# dcdc_0421.net
KiCad netlist of a schematic drawn in EAGLE
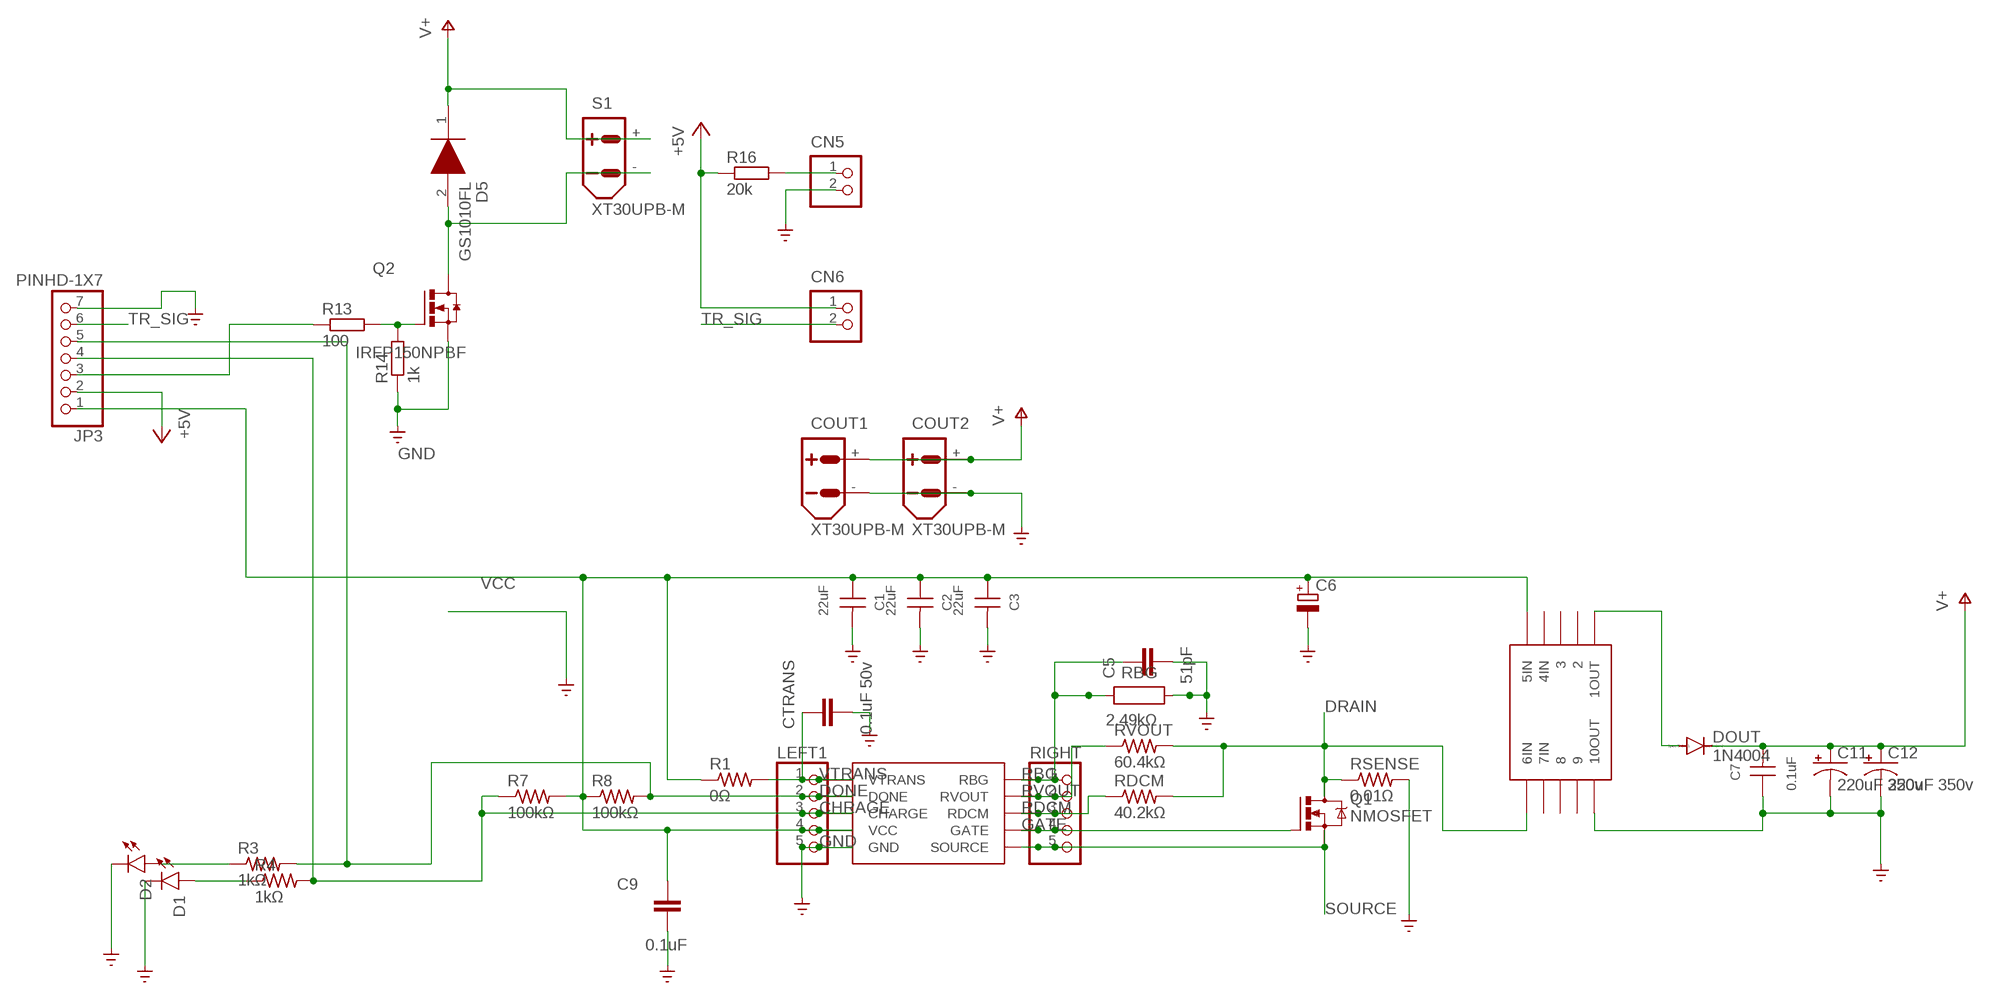
[diagram p0: schematic, sheet 1]

(export (version "E")
  (design (tool "Eeschema 10.0.6"))
  (components
    (comp (ref "C1")
      (value "22uF")
      (footprint "eagle-import:WCAP-CSGP_1210_H0.95")
      (libsource (lib "eagle-import") (part "WCAP-CSGP_1210_H0.95_25V(DC)_885012009002"))
    )
    (comp (ref "C2")
      (value "22uF")
      (footprint "eagle-import:WCAP-CSGP_1210_H0.95")
      (libsource (lib "eagle-import") (part "WCAP-CSGP_1210_H0.95_25V(DC)_885012009002"))
    )
    (comp (ref "C3")
      (value "22uF")
      (footprint "eagle-import:WCAP-CSGP_1210_H0.95")
      (libsource (lib "eagle-import") (part "WCAP-CSGP_1210_H0.95_25V(DC)_885012009002"))
    )
    (comp (ref "C5")
      (value "51pF")
      (footprint "eagle-import:CAP_0603")
      (fields
        (field (name "DIGIKEY_PART_NUMBER") "399-7814-2-ND")
        (field (name "MANUFACTURER") "KEMET")
        (field (name "MPN") "C0603C100C5GACTU")
        (field (name "CREATED_BY") "PCBLayout.com")
      )
      (libsource (lib "eagle-import") (part "C0603C100C5GACTU"))
    )
    (comp (ref "C6")
      (value "CPOL-EUTT2D6")
      (footprint "eagle-import:TT2D6")
      (libsource (lib "eagle-import") (part "CPOL-EUTT2D6"))
    )
    (comp (ref "C7")
      (value "0.1uF")
      (footprint "eagle-import:WCAP-CSGP_1812_H1.25")
      (libsource (lib "eagle-import") (part "WCAP-CSGP_1812_H1.25_16V(DC)_885012010001"))
    )
    (comp (ref "C9")
      (value "0.1uF")
      (footprint "eagle-import:CAP_0603")
      (fields
        (field (name "DIGIKEY_PART_NUMBER") "399-7814-2-ND")
        (field (name "MANUFACTURER") "KEMET")
        (field (name "MPN") "C0603C100C5GACTU")
        (field (name "CREATED_BY") "PCBLayout.com")
      )
      (libsource (lib "eagle-import") (part "C0603C100C5GACTU"))
    )
    (comp (ref "C11")
      (value "220uF 350v")
      (footprint "eagle-import:E7,5-18")
      (libsource (lib "eagle-import") (part "CAPACITOR-PE7.5-18"))
    )
    (comp (ref "C12")
      (value "220uF 350v")
      (footprint "eagle-import:E7,5-18")
      (libsource (lib "eagle-import") (part "CAPACITOR-PE7.5-18"))
    )
    (comp (ref "CN5")
      (value "S2B-XH-A")
      (footprint "eagle-import:S2B-XH-A")
      (libsource (lib "eagle-import") (part "S2B-XH-A"))
    )
    (comp (ref "CN6")
      (value "S2B-XH-A")
      (footprint "eagle-import:S2B-XH-A")
      (libsource (lib "eagle-import") (part "S2B-XH-A"))
    )
    (comp (ref "COUT1")
      (value "XT30UPB-M")
      (footprint "eagle-import:XT30UPB-M")
      (libsource (lib "eagle-import") (part "XT30UPB-M"))
    )
    (comp (ref "COUT2")
      (value "XT30UPB-M")
      (footprint "eagle-import:XT30UPB-M")
      (libsource (lib "eagle-import") (part "XT30UPB-M"))
    )
    (comp (ref "CTRANS")
      (value "0.1uF 50v")
      (footprint "eagle-import:CAP_1206")
      (fields
        (field (name "DIGIKEY_PART_NUMBER") "GRM31CR60J107ME39L")
        (field (name "MANUFACTURER") "Murata Electronics North America")
        (field (name "CREATED_BY") "PCBLayout.com")
      )
      (libsource (lib "eagle-import") (part "GRM31CR60J107ME39L"))
    )
    (comp (ref "D1")
      (value "LED_RADIALWHITE")
      (footprint "eagle-import:LEDRD254W60D565H860B_W")
      (libsource (lib "eagle-import") (part "LED_RADIALWHITE"))
    )
    (comp (ref "D2")
      (value "LED_RADIALWHITE")
      (footprint "eagle-import:LEDRD254W60D565H860B_W")
      (libsource (lib "eagle-import") (part "LED_RADIALWHITE"))
    )
    (comp (ref "D5")
      (value "GS1010FL")
      (footprint "eagle-import:SODFL3618X110N")
      (libsource (lib "eagle-import") (part "GS1010FL"))
    )
    (comp (ref "DOUT")
      (value "1N4004")
      (footprint "eagle-import:DO41-10")
      (libsource (lib "eagle-import") (part "1N4004"))
    )
    (comp (ref "JP3")
      (value "PINHD-1X7")
      (footprint "eagle-import:1X07")
      (libsource (lib "eagle-import") (part "PINHD-1X7"))
    )
    (comp (ref "LEFT1")
      (value "PINHD-1X5")
      (footprint "eagle-import:1X05")
      (libsource (lib "eagle-import") (part "PINHD-1X5"))
    )
    (comp (ref "Q1")
      (value "NMOSFET")
      (footprint "eagle-import:TO220BV")
      (libsource (lib "eagle-import") (part "NMOSFET_TO220_"))
    )
    (comp (ref "Q2")
      (value "IRFP150NPBF")
      (footprint "eagle-import:TO-247AC")
      (fields
        (field (name "DIGIKEY_PART_NUMBER") "IRFP150NPBF-ND")
        (field (name "CREATED_BY") "PCBLayout.com")
      )
      (libsource (lib "eagle-import") (part "IRFP150NPBF"))
    )
    (comp (ref "R1")
      (value "0Ω")
      (footprint "eagle-import:M2012")
      (libsource (lib "eagle-import") (part "R-US_M2012"))
    )
    (comp (ref "R3")
      (value "1kΩ")
      (footprint "eagle-import:RES_0402")
      (fields
        (field (name "DIGIKEY_PART_NUMBER") "311-0.0JRTR-ND")
        (field (name "MANUFACTURER") "Yageo")
        (field (name "MPN") "RC0402JR-070RL")
        (field (name "CREATED_BY") "PCBLayout.com")
      )
      (libsource (lib "eagle-import") (part "RC0402JR-070RL"))
    )
    (comp (ref "R4")
      (value "1kΩ")
      (footprint "eagle-import:RES_0402")
      (fields
        (field (name "DIGIKEY_PART_NUMBER") "311-0.0JRTR-ND")
        (field (name "MANUFACTURER") "Yageo")
        (field (name "MPN") "RC0402JR-070RL")
        (field (name "CREATED_BY") "PCBLayout.com")
      )
      (libsource (lib "eagle-import") (part "RC0402JR-070RL"))
    )
    (comp (ref "R7")
      (value "100kΩ")
      (footprint "eagle-import:R1210")
      (libsource (lib "eagle-import") (part "R-US_R1210"))
    )
    (comp (ref "R8")
      (value "100kΩ")
      (footprint "eagle-import:R1210")
      (libsource (lib "eagle-import") (part "R-US_R1210"))
    )
    (comp (ref "R13")
      (value "100")
      (footprint "eagle-import:R0603")
      (libsource (lib "eagle-import") (part "R-EU_R0603"))
    )
    (comp (ref "R14")
      (value "1k")
      (footprint "eagle-import:R0603")
      (libsource (lib "eagle-import") (part "R-EU_R0603"))
    )
    (comp (ref "R16")
      (value "20k")
      (footprint "eagle-import:R0603")
      (libsource (lib "eagle-import") (part "R-EU_R0603"))
    )
    (comp (ref "RBG")
      (value "2.49kΩ")
      (footprint "eagle-import:WRIS_PSMC_2512_6.3X3.1X0.51X1.1(LXWXHXPW)")
      (libsource (lib "eagle-import") (part "WRIS-PSMC_2512_6.3X3.1X0.51X1.1_580070763005"))
    )
    (comp (ref "RDCM")
      (value "40.2kΩ")
      (footprint "eagle-import:RES_0805")
      (fields
        (field (name "DIGIKEY_PART_NUMBER") "541-0.0ATR-ND")
        (field (name "MANUFACTURER") "Vishay Dale")
        (field (name "MPN") "CRCW08050000Z0EA")
        (field (name "CREATED_BY") "PCBLayout.com")
      )
      (libsource (lib "eagle-import") (part "CRCW08050000Z0EA"))
    )
    (comp (ref "RIGHT")
      (value "PINHD-1X5")
      (footprint "eagle-import:1X05")
      (libsource (lib "eagle-import") (part "PINHD-1X5"))
    )
    (comp (ref "RSENSE")
      (value "0.01Ω")
      (footprint "eagle-import:RES_1206")
      (fields
        (field (name "DIGIKEY_PART_NUMBER") "WSLP-.05TR-ND")
        (field (name "MANUFACTURER") "Vishay Dale")
        (field (name "MPN") "WSLP1206R0500FEA")
        (field (name "CREATED_BY") "PCBLayout.com")
      )
      (libsource (lib "eagle-import") (part "WSLP1206R0500FEA"))
    )
    (comp (ref "RVOUT")
      (value "60.4kΩ")
      (footprint "eagle-import:RES_0805")
      (fields
        (field (name "DIGIKEY_PART_NUMBER") "541-0.0ATR-ND")
        (field (name "MANUFACTURER") "Vishay Dale")
        (field (name "MPN") "CRCW08050000Z0EA")
        (field (name "CREATED_BY") "PCBLayout.com")
      )
      (libsource (lib "eagle-import") (part "CRCW08050000Z0EA"))
    )
    (comp (ref "S1")
      (value "XT30UPB-M")
      (footprint "eagle-import:XT30UPB-M")
      (libsource (lib "eagle-import") (part "XT30UPB-M"))
    )
    (comp (ref "U$1")
      (value "LT3750_2")
      (footprint "eagle-import:LT3750_2")
      (libsource (lib "eagle-import") (part "LT3750_2"))
    )
    (comp (ref "U$2")
      (value "32052")
      (footprint "eagle-import:32052")
      (libsource (lib "eagle-import") (part "32052"))
    )
  )
  (nets
    (net (code "1") (name "+5V") (class "Default")
      (node (ref "CN6") (pin "1") (pinfunction "1_1") (pintype "passive"))
      (node (ref "JP3") (pin "2") (pinfunction "2_2") (pintype "passive"))
      (node (ref "R16") (pin "1") (pinfunction "1_1") (pintype "passive"))
    )
    (net (code "2") (name "/CHRAGE") (class "Default")
      (node (ref "JP3") (pin "4") (pinfunction "4_4") (pintype "passive"))
      (node (ref "LEFT1") (pin "3") (pinfunction "3_3") (pintype "passive"))
      (node (ref "R4") (pin "2") (pinfunction "2_2") (pintype "passive"))
      (node (ref "R7") (pin "1") (pinfunction "1_1") (pintype "passive"))
      (node (ref "U$1") (pin "CHARGE") (pinfunction "CHARGE_CHARGE") (pintype "bidirectional"))
    )
    (net (code "3") (name "/DONE") (class "Default")
      (node (ref "JP3") (pin "5") (pinfunction "5_5") (pintype "passive"))
      (node (ref "LEFT1") (pin "2") (pinfunction "2_2") (pintype "passive"))
      (node (ref "R3") (pin "2") (pinfunction "2_2") (pintype "passive"))
      (node (ref "R8") (pin "2") (pinfunction "2_2") (pintype "passive"))
      (node (ref "U$1") (pin "DONE") (pinfunction "DONE_DONE") (pintype "bidirectional"))
    )
    (net (code "4") (name "/DRAIN") (class "Default")
      (node (ref "Q1") (pin "D") (pinfunction "D_D") (pintype "passive"))
      (node (ref "RDCM") (pin "2") (pinfunction "2_2") (pintype "passive"))
      (node (ref "RSENSE") (pin "1") (pinfunction "1_1") (pintype "passive"))
      (node (ref "RVOUT") (pin "2") (pinfunction "2_2") (pintype "passive"))
      (node (ref "U$2") (pin "6IN") (pinfunction "6IN_6IN") (pintype "bidirectional"))
    )
    (net (code "5") (name "/GATE") (class "Default")
      (node (ref "Q1") (pin "G") (pinfunction "G_G") (pintype "passive"))
      (node (ref "RIGHT") (pin "4") (pinfunction "4_4") (pintype "passive"))
      (node (ref "U$1") (pin "GATE") (pinfunction "GATE_GATE") (pintype "bidirectional"))
    )
    (net (code "6") (name "/RBG") (class "Default")
      (node (ref "C5") (pin "1") (pinfunction "1_1") (pintype "passive"))
      (node (ref "RBG") (pin "1") (pinfunction "1_1") (pintype "passive"))
      (node (ref "RIGHT") (pin "1") (pinfunction "1_1") (pintype "passive"))
      (node (ref "U$1") (pin "RBG") (pinfunction "RBG_RBG") (pintype "bidirectional"))
    )
    (net (code "7") (name "/RDCM") (class "Default")
      (node (ref "RDCM") (pin "1") (pinfunction "1_1") (pintype "passive"))
      (node (ref "RIGHT") (pin "3") (pinfunction "3_3") (pintype "passive"))
      (node (ref "U$1") (pin "RDCM") (pinfunction "RDCM_RDCM") (pintype "bidirectional"))
    )
    (net (code "8") (name "/RVOUT") (class "Default")
      (node (ref "RIGHT") (pin "2") (pinfunction "2_2") (pintype "passive"))
      (node (ref "RVOUT") (pin "1") (pinfunction "1_1") (pintype "passive"))
      (node (ref "U$1") (pin "RVOUT") (pinfunction "RVOUT_RVOUT") (pintype "bidirectional"))
    )
    (net (code "9") (name "/SOURCE") (class "Default")
      (node (ref "Q1") (pin "S") (pinfunction "S_S") (pintype "passive"))
      (node (ref "RIGHT") (pin "5") (pinfunction "5_5") (pintype "passive"))
      (node (ref "U$1") (pin "SOURCE") (pinfunction "SOURCE_SOURCE") (pintype "bidirectional"))
    )
    (net (code "10") (name "/TR_SIG") (class "Default")
      (node (ref "CN6") (pin "2") (pinfunction "2_2") (pintype "passive"))
      (node (ref "JP3") (pin "6") (pinfunction "6_6") (pintype "passive"))
    )
    (net (code "11") (name "/VCC") (class "Default")
      (node (ref "C1") (pin "1") (pinfunction "1_1") (pintype "passive"))
      (node (ref "C2") (pin "1") (pinfunction "1_1") (pintype "passive"))
      (node (ref "C3") (pin "1") (pinfunction "1_1") (pintype "passive"))
      (node (ref "C6") (pin "+") (pinfunction "+_+") (pintype "passive"))
      (node (ref "C9") (pin "1") (pinfunction "1_1") (pintype "passive"))
      (node (ref "JP3") (pin "1") (pinfunction "1_1") (pintype "passive"))
      (node (ref "LEFT1") (pin "4") (pinfunction "4_4") (pintype "passive"))
      (node (ref "R1") (pin "1") (pinfunction "1_1") (pintype "passive"))
      (node (ref "R7") (pin "2") (pinfunction "2_2") (pintype "passive"))
      (node (ref "R8") (pin "1") (pinfunction "1_1") (pintype "passive"))
      (node (ref "U$1") (pin "VCC") (pinfunction "VCC_VCC") (pintype "bidirectional"))
      (node (ref "U$2") (pin "5IN") (pinfunction "5IN_5IN") (pintype "bidirectional"))
    )
    (net (code "12") (name "/VTRANS") (class "Default")
      (node (ref "CTRANS") (pin "1") (pinfunction "1_1") (pintype "passive"))
      (node (ref "LEFT1") (pin "1") (pinfunction "1_1") (pintype "passive"))
      (node (ref "R1") (pin "2") (pinfunction "2_2") (pintype "passive"))
      (node (ref "U$1") (pin "VTRANS") (pinfunction "VTRANS_VTRANS") (pintype "bidirectional"))
    )
    (net (code "13") (name "Net-(CN5-Pad1)") (class "Default")
      (node (ref "CN5") (pin "1") (pinfunction "1_1") (pintype "passive"))
      (node (ref "R16") (pin "2") (pinfunction "2_2") (pintype "passive"))
    )
    (net (code "14") (name "Net-(D1-PadA)") (class "Default")
      (node (ref "D1") (pin "A") (pinfunction "A_A") (pintype "passive"))
      (node (ref "R4") (pin "1") (pinfunction "1_1") (pintype "passive"))
    )
    (net (code "15") (name "Net-(D2-PadA)") (class "Default")
      (node (ref "D2") (pin "A") (pinfunction "A_A") (pintype "passive"))
      (node (ref "R3") (pin "1") (pinfunction "1_1") (pintype "passive"))
    )
    (net (code "16") (name "Net-(D5-A)") (class "Default")
      (node (ref "D5") (pin "2") (pinfunction "A_2") (pintype "bidirectional"))
      (node (ref "Q2") (pin "D") (pinfunction "D_D") (pintype "passive"))
      (node (ref "S1") (pin "-") (pinfunction "-_-") (pintype "power_in"))
    )
    (net (code "17") (name "Net-(DOUT-PadA)") (class "Default")
      (node (ref "DOUT") (pin "A") (pinfunction "A_A") (pintype "passive"))
      (node (ref "U$2") (pin "1OUT") (pinfunction "1OUT_1OUT") (pintype "bidirectional"))
    )
    (net (code "18") (name "Net-(JP3-Pad3)") (class "Default")
      (node (ref "JP3") (pin "3") (pinfunction "3_3") (pintype "passive"))
      (node (ref "R13") (pin "1") (pinfunction "1_1") (pintype "passive"))
    )
    (net (code "19") (name "Net-(Q2-PadG)") (class "Default")
      (node (ref "Q2") (pin "G") (pinfunction "G_G") (pintype "passive"))
      (node (ref "R13") (pin "2") (pinfunction "2_2") (pintype "passive"))
      (node (ref "R14") (pin "2") (pinfunction "2_2") (pintype "passive"))
    )
    (net (code "20") (name "SUPPLY0_GND_") (class "Default")
      (node (ref "C1") (pin "2") (pinfunction "2_2") (pintype "passive"))
      (node (ref "C11") (pin "-") (pinfunction "-_-") (pintype "passive"))
      (node (ref "C12") (pin "-") (pinfunction "-_-") (pintype "passive"))
      (node (ref "C2") (pin "2") (pinfunction "2_2") (pintype "passive"))
      (node (ref "C3") (pin "2") (pinfunction "2_2") (pintype "passive"))
      (node (ref "C5") (pin "2") (pinfunction "2_2") (pintype "passive"))
      (node (ref "C6") (pin "-") (pinfunction "-_-") (pintype "passive"))
      (node (ref "C7") (pin "1") (pinfunction "1_1") (pintype "passive"))
      (node (ref "C9") (pin "2") (pinfunction "2_2") (pintype "passive"))
      (node (ref "CN5") (pin "2") (pinfunction "2_2") (pintype "passive"))
      (node (ref "COUT1") (pin "-") (pinfunction "-_-") (pintype "power_in"))
      (node (ref "COUT2") (pin "-") (pinfunction "-_-") (pintype "power_in"))
      (node (ref "CTRANS") (pin "2") (pinfunction "2_2") (pintype "passive"))
      (node (ref "D1") (pin "C") (pinfunction "C_C") (pintype "passive"))
      (node (ref "D2") (pin "C") (pinfunction "C_C") (pintype "passive"))
      (node (ref "JP3") (pin "7") (pinfunction "7_7") (pintype "passive"))
      (node (ref "LEFT1") (pin "5") (pinfunction "5_5") (pintype "passive"))
      (node (ref "Q2") (pin "S") (pinfunction "S_S") (pintype "passive"))
      (node (ref "R14") (pin "1") (pinfunction "1_1") (pintype "passive"))
      (node (ref "RBG") (pin "2") (pinfunction "2_2") (pintype "passive"))
      (node (ref "RSENSE") (pin "2") (pinfunction "2_2") (pintype "passive"))
      (node (ref "U$1") (pin "GND") (pinfunction "GND_GND") (pintype "bidirectional"))
      (node (ref "U$2") (pin "10OUT") (pinfunction "10OUT_10OUT") (pintype "bidirectional"))
    )
    (net (code "21") (name "V+") (class "Default")
      (node (ref "C11") (pin "+") (pinfunction "+_+") (pintype "passive"))
      (node (ref "C12") (pin "+") (pinfunction "+_+") (pintype "passive"))
      (node (ref "C7") (pin "2") (pinfunction "2_2") (pintype "passive"))
      (node (ref "COUT1") (pin "+") (pinfunction "+_+") (pintype "power_in"))
      (node (ref "COUT2") (pin "+") (pinfunction "+_+") (pintype "power_in"))
      (node (ref "D5") (pin "1") (pinfunction "K_1") (pintype "bidirectional"))
      (node (ref "DOUT") (pin "C") (pinfunction "C_C") (pintype "passive"))
      (node (ref "S1") (pin "+") (pinfunction "+_+") (pintype "power_in"))
    )
    (net (code "22") (name "unconnected-(U$2-Pad2)") (class "Default")
      (node (ref "U$2") (pin "2") (pinfunction "2_2") (pintype "bidirectional"))
    )
    (net (code "23") (name "unconnected-(U$2-Pad3)") (class "Default")
      (node (ref "U$2") (pin "3") (pinfunction "3_3") (pintype "bidirectional"))
    )
    (net (code "24") (name "unconnected-(U$2-Pad4IN)") (class "Default")
      (node (ref "U$2") (pin "4IN") (pinfunction "4IN_4IN") (pintype "bidirectional"))
    )
    (net (code "25") (name "unconnected-(U$2-Pad7IN)") (class "Default")
      (node (ref "U$2") (pin "7IN") (pinfunction "7IN_7IN") (pintype "bidirectional"))
    )
    (net (code "26") (name "unconnected-(U$2-Pad8)") (class "Default")
      (node (ref "U$2") (pin "8") (pinfunction "8_8") (pintype "bidirectional"))
    )
    (net (code "27") (name "unconnected-(U$2-Pad9)") (class "Default")
      (node (ref "U$2") (pin "9") (pinfunction "9_9") (pintype "bidirectional"))
    )
  )
)
